# BNO055.net
KiCad netlist of a schematic drawn in Altium Designer
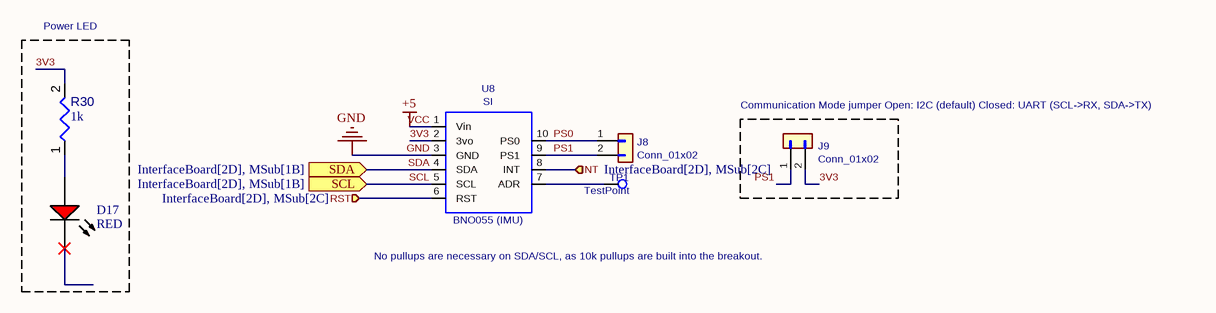
[diagram p0: BNO055.SchDoc]

(export (version "E")
  (design (tool "Eeschema 10.0.6"))
  (components
    (comp (ref "D17")
      (value "RED")
      (footprint "LTST-C191KRKT_V")
      (description "LED Uni-Color Red, 62.5 mW, 25 mA, -30 to 85 degC, 2-Pin SMD, RoHS, Tape and Reel")
      (fields (field (name "POWER") "75mW") (field (name "MANUFACTURER") "Lite-On"))
      (libsource (lib "Isaac Lee Altium Cloud") (part "LED-RED-AK-2"))
    )
    (comp (ref "J8") (value "Conn_01x02") (footprint "HDR1X2") (libsource (lib "") (part "Conn_01x02_1")))
    (comp (ref "J9")
      (value "Conn_01x02")
      (footprint "HDR1X2")
      (libsource (lib "Connector_Generic") (part "Conn_01x02"))
    )
    (comp (ref "R30")
      (value "1k")
      (footprint "RESC1608X55X25ML10T15")
      (description "Chip Resistor, 1 KOhm, +/-1%, 0.1 W, -55 to 155 degC, 0603 (1608 Metric)")
      (fields (field (name "POWER") "100mW") (field (name "TOLERANCE") "1%"))
      (libsource (lib "Isaac Lee Altium Cloud") (part "RES-2"))
    )
    (comp (ref "TP1")
      (value "TestPoint")
      (footprint "Test Point")
      (libsource (lib "Connector") (part "TestPoint"))
    )
    (comp (ref "U8")
      (value "SI")
      (footprint "BNO055 Adafruit Breakout")
      (libsource (lib "Sprite_Sensors") (part "SI"))
    )
  )
  (nets
    (net (code "1") (name "+5") (class "Default")
      (node (ref "U8") (pin "1") (pinfunction "Vin_1") (pintype "passive"))
    )
    (net (code "2") (name "/3V3") (class "Default")
      (node (ref "J9") (pin "2") (pinfunction "Pin_2_2") (pintype "passive"))
      (node (ref "R30") (pin "2") (pinfunction "2_2") (pintype "passive"))
      (node (ref "U8") (pin "2") (pinfunction "3vo_2") (pintype "passive"))
    )
    (net (code "3") (name "/INT") (class "Default")
      (node (ref "U8") (pin "8") (pinfunction "INT_8") (pintype "passive"))
    )
    (net (code "4") (name "/PS0") (class "Default")
      (node (ref "J8") (pin "1") (pinfunction "Pin_1_1") (pintype "passive"))
      (node (ref "U8") (pin "10") (pinfunction "PS0_10") (pintype "passive"))
    )
    (net (code "5") (name "/PS1") (class "Default")
      (node (ref "J8") (pin "2") (pinfunction "Pin_2_2") (pintype "passive"))
      (node (ref "J9") (pin "1") (pinfunction "Pin_1_1") (pintype "passive"))
      (node (ref "U8") (pin "9") (pinfunction "PS1_9") (pintype "passive"))
    )
    (net (code "6") (name "/RST") (class "Default")
      (node (ref "U8") (pin "6") (pinfunction "RST_6") (pintype "passive"))
    )
    (net (code "7") (name "/SCL") (class "Default")
      (node (ref "U8") (pin "5") (pinfunction "SCL_5") (pintype "passive"))
    )
    (net (code "8") (name "/SDA") (class "Default")
      (node (ref "U8") (pin "4") (pinfunction "SDA_4") (pintype "passive"))
    )
    (net (code "9") (name "GND") (class "Default")
      (node (ref "U8") (pin "3") (pinfunction "GND_3") (pintype "passive"))
    )
    (net (code "10") (name "Net-(D17-A)") (class "Default")
      (node (ref "D17") (pin "1") (pinfunction "A_1") (pintype "passive"))
      (node (ref "R30") (pin "1") (pinfunction "1_1") (pintype "passive"))
    )
    (net (code "11") (name "Net-(U8-ADR)") (class "Default")
      (node (ref "TP1") (pin "1") (pinfunction "1_1") (pintype "passive"))
      (node (ref "U8") (pin "7") (pinfunction "ADR_7") (pintype "passive"))
    )
    (net (code "12") (name "unconnected-(D17-K-Pad2)") (class "Default")
      (node (ref "D17") (pin "2") (pinfunction "K_2") (pintype "passive+no_connect"))
    )
  )
)
